# placamaxpequena.net
KiCad netlist of a schematic drawn in EAGLE
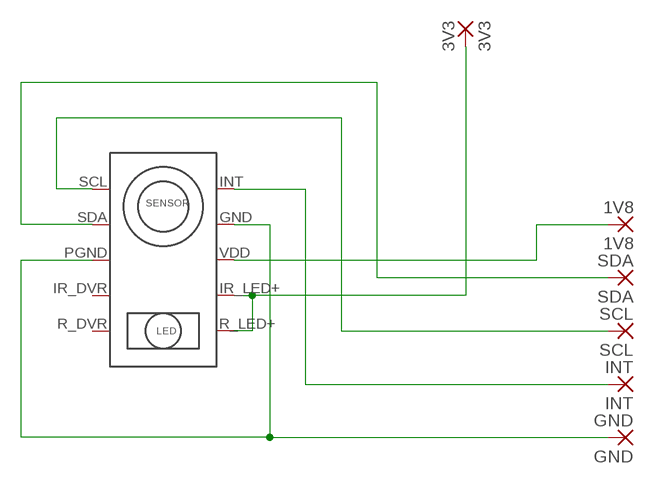
[diagram p0: schematic, sheet 1]

(export (version "E")
  (design (tool "Eeschema 10.0.6"))
  (components
    (comp (ref "1V8")
      (value "1V8")
      (footprint "eagle-import:SMD1,27-2,54")
      (libsource (lib "eagle-import") (part "WIREPADSMD1,27-254"))
    )
    (comp (ref "3V3")
      (value "3V3")
      (footprint "eagle-import:SMD1,27-2,54")
      (libsource (lib "eagle-import") (part "WIREPADSMD1,27-254"))
    )
    (comp (ref "GND")
      (value "GND")
      (footprint "eagle-import:SMD1,27-2,54")
      (libsource (lib "eagle-import") (part "WIREPADSMD1,27-254"))
    )
    (comp (ref "INT")
      (value "INT")
      (footprint "eagle-import:SMD1,27-2,54")
      (libsource (lib "eagle-import") (part "WIREPADSMD1,27-254"))
    )
    (comp (ref "SCL")
      (value "SCL")
      (footprint "eagle-import:SMD1,27-2,54")
      (libsource (lib "eagle-import") (part "WIREPADSMD1,27-254"))
    )
    (comp (ref "SDA")
      (value "SDA")
      (footprint "eagle-import:SMD1,27-2,54")
      (libsource (lib "eagle-import") (part "WIREPADSMD1,27-254"))
    )
    (comp (ref "U$1")
      (value "MAX30100")
      (footprint "eagle-import:SOIC14")
      (libsource (lib "eagle-import") (part "MAX30100"))
    )
  )
  (nets
    (net (code "1") (name "Net-(1V8-P)") (class "Default")
      (node (ref "1V8") (pin "1") (pinfunction "P_1") (pintype "passive"))
      (node (ref "U$1") (pin "VDD") (pinfunction "VDD_VDD") (pintype "power_in"))
    )
    (net (code "2") (name "Net-(3V3-P)") (class "Default")
      (node (ref "3V3") (pin "1") (pinfunction "P_1") (pintype "passive"))
      (node (ref "U$1") (pin "IR_LED+") (pinfunction "IR_LED+_IR_LED+") (pintype "bidirectional"))
      (node (ref "U$1") (pin "R_LED+") (pinfunction "R_LED+_R_LED+") (pintype "bidirectional"))
    )
    (net (code "3") (name "Net-(GND-P)") (class "Default")
      (node (ref "GND") (pin "1") (pinfunction "P_1") (pintype "passive"))
      (node (ref "U$1") (pin "GND") (pinfunction "GND_GND") (pintype "power_in"))
      (node (ref "U$1") (pin "PGND") (pinfunction "PGND_PGND") (pintype "power_in"))
    )
    (net (code "4") (name "Net-(INT-P)") (class "Default")
      (node (ref "INT") (pin "1") (pinfunction "P_1") (pintype "passive"))
      (node (ref "U$1") (pin "INT") (pinfunction "INT_INT") (pintype "bidirectional"))
    )
    (net (code "5") (name "Net-(SCL-P)") (class "Default")
      (node (ref "SCL") (pin "1") (pinfunction "P_1") (pintype "passive"))
      (node (ref "U$1") (pin "SCL") (pinfunction "SCL_SCL") (pintype "bidirectional"))
    )
    (net (code "6") (name "Net-(SDA-P)") (class "Default")
      (node (ref "SDA") (pin "1") (pinfunction "P_1") (pintype "passive"))
      (node (ref "U$1") (pin "SDA") (pinfunction "SDA_SDA") (pintype "bidirectional"))
    )
    (net (code "7") (name "unconnected-(U$1-PadIR_DVR)") (class "Default")
      (node (ref "U$1") (pin "IR_DVR") (pinfunction "IR_DVR_IR_DVR") (pintype "bidirectional"))
    )
    (net (code "8") (name "unconnected-(U$1-PadR_DVR)") (class "Default")
      (node (ref "U$1") (pin "R_DVR") (pinfunction "R_DVR_R_DVR") (pintype "bidirectional"))
    )
  )
)
